# Plumbing.net
KiCad netlist of a schematic drawn in Altium Designer
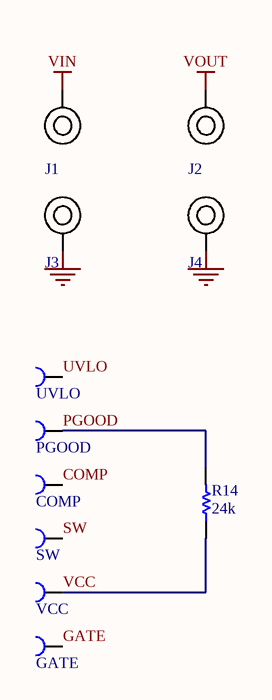
[diagram p0: Plumbing.SchDoc]

(export (version "E")
  (design (tool "Eeschema 10.0.6"))
  (components
    (comp (ref "COMP")
      (value "SMD test point")
      (footprint "2mm SMD test point")
      (libsource (lib "Connectors") (part "SMD test point"))
    )
    (comp (ref "GATE")
      (value "SMD test point")
      (footprint "2mm SMD test point")
      (libsource (lib "Connectors") (part "SMD test point"))
    )
    (comp (ref "J1")
      (value "575-8")
      (footprint "575-8")
      (description "Keystone PCB banana jack")
      (libsource (lib "Connectors") (part "575-8"))
    )
    (comp (ref "J2")
      (value "575-8")
      (footprint "575-8")
      (description "Keystone PCB banana jack")
      (libsource (lib "Connectors") (part "575-8"))
    )
    (comp (ref "J3")
      (value "575-8")
      (footprint "575-8")
      (description "Keystone PCB banana jack")
      (libsource (lib "Connectors") (part "575-8"))
    )
    (comp (ref "J4")
      (value "575-8")
      (footprint "575-8")
      (description "Keystone PCB banana jack")
      (libsource (lib "Connectors") (part "575-8"))
    )
    (comp (ref "PGOOD")
      (value "SMD test point")
      (footprint "2mm SMD test point")
      (libsource (lib "Connectors") (part "SMD test point"))
    )
    (comp (ref "R14")
      (value "24k")
      (footprint "RESC0603(1608)_N")
      (description "RES SMD 24K OHM 1% 1/10W 0603")
      (fields
        (field (name "MANUFACTURER") "Yageo")
        (field (name "MANUFACTURER PART NUMBER") "RC0603FR-0724KL")
      )
      (libsource (lib "0603 Resistors") (part "RC0603FR-0724KL"))
    )
    (comp (ref "SW")
      (value "SMD test point")
      (footprint "2mm SMD test point")
      (libsource (lib "Connectors") (part "SMD test point"))
    )
    (comp (ref "UVLO")
      (value "SMD test point")
      (footprint "2mm SMD test point")
      (libsource (lib "Connectors") (part "SMD test point"))
    )
    (comp (ref "VCC")
      (value "SMD test point")
      (footprint "2mm SMD test point")
      (libsource (lib "Connectors") (part "SMD test point"))
    )
  )
  (nets
    (net (code "1") (name "/COMP") (class "Default")
      (node (ref "COMP") (pin "1") (pinfunction "1_1") (pintype "passive"))
    )
    (net (code "2") (name "/GATE") (class "Default")
      (node (ref "GATE") (pin "1") (pinfunction "1_1") (pintype "passive"))
    )
    (net (code "3") (name "/PGOOD") (class "Default")
      (node (ref "PGOOD") (pin "1") (pinfunction "1_1") (pintype "passive"))
      (node (ref "R14") (pin "2") (pinfunction "2_2") (pintype "passive"))
    )
    (net (code "4") (name "/SW") (class "Default")
      (node (ref "SW") (pin "1") (pinfunction "1_1") (pintype "passive"))
    )
    (net (code "5") (name "/UVLO") (class "Default")
      (node (ref "UVLO") (pin "1") (pinfunction "1_1") (pintype "passive"))
    )
    (net (code "6") (name "/VCC") (class "Default")
      (node (ref "R14") (pin "1") (pinfunction "1_1") (pintype "passive"))
      (node (ref "VCC") (pin "1") (pinfunction "1_1") (pintype "passive"))
    )
    (net (code "7") (name "GND") (class "Default")
      (node (ref "J3") (pin "1") (pinfunction "1_1") (pintype "passive"))
      (node (ref "J4") (pin "1") (pinfunction "1_1") (pintype "passive"))
    )
    (net (code "8") (name "VIN") (class "Default")
      (node (ref "J1") (pin "1") (pinfunction "1_1") (pintype "passive"))
    )
    (net (code "9") (name "VOUT") (class "Default")
      (node (ref "J2") (pin "1") (pinfunction "1_1") (pintype "passive"))
    )
  )
)
